# RECEPTOR_AIS_BLK_R00.net
KiCad netlist of a schematic drawn in Altium Designer
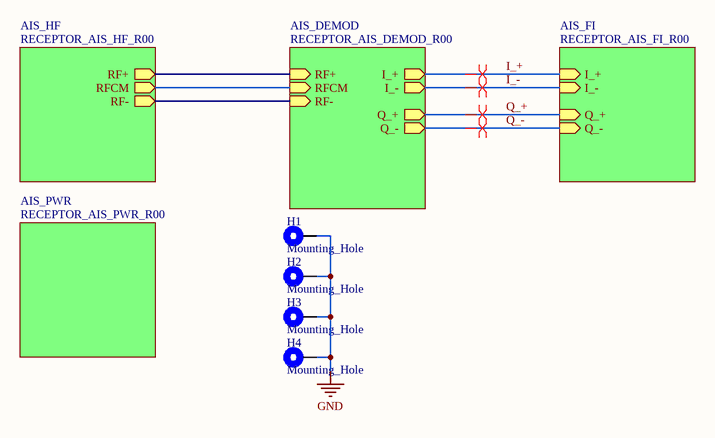
[diagram p0: RECEPTOR_AIS_BLK_R00.SchDoc]

(export (version "E")
  (design (tool "Eeschema 10.0.6"))
  (components
    (comp (ref "H1")
      (value "Mounting_Hole")
      (footprint "Mounting_Hole_M2")
      (libsource (lib "RECEPTOR_AIS_R00") (part "Mounting_Hole"))
    )
    (comp (ref "H2")
      (value "Mounting_Hole")
      (footprint "Mounting_Hole_M2")
      (libsource (lib "RECEPTOR_AIS_R00") (part "Mounting_Hole"))
    )
    (comp (ref "H3")
      (value "Mounting_Hole")
      (footprint "Mounting_Hole_M2")
      (libsource (lib "RECEPTOR_AIS_R00") (part "Mounting_Hole"))
    )
    (comp (ref "H4")
      (value "Mounting_Hole")
      (footprint "Mounting_Hole_M2")
      (libsource (lib "RECEPTOR_AIS_R00") (part "Mounting_Hole"))
    )
  )
  (nets
    (net (code "8") (name "GND") (class "Default")
      (node (ref "H1") (pin "1") (pinfunction "1_1") (pintype "power_in"))
      (node (ref "H2") (pin "1") (pinfunction "1_1") (pintype "power_in"))
      (node (ref "H3") (pin "1") (pinfunction "1_1") (pintype "power_in"))
      (node (ref "H4") (pin "1") (pinfunction "1_1") (pintype "power_in"))
    )
  )
)
